# POWER.net
KiCad netlist of a schematic drawn in Altium Designer
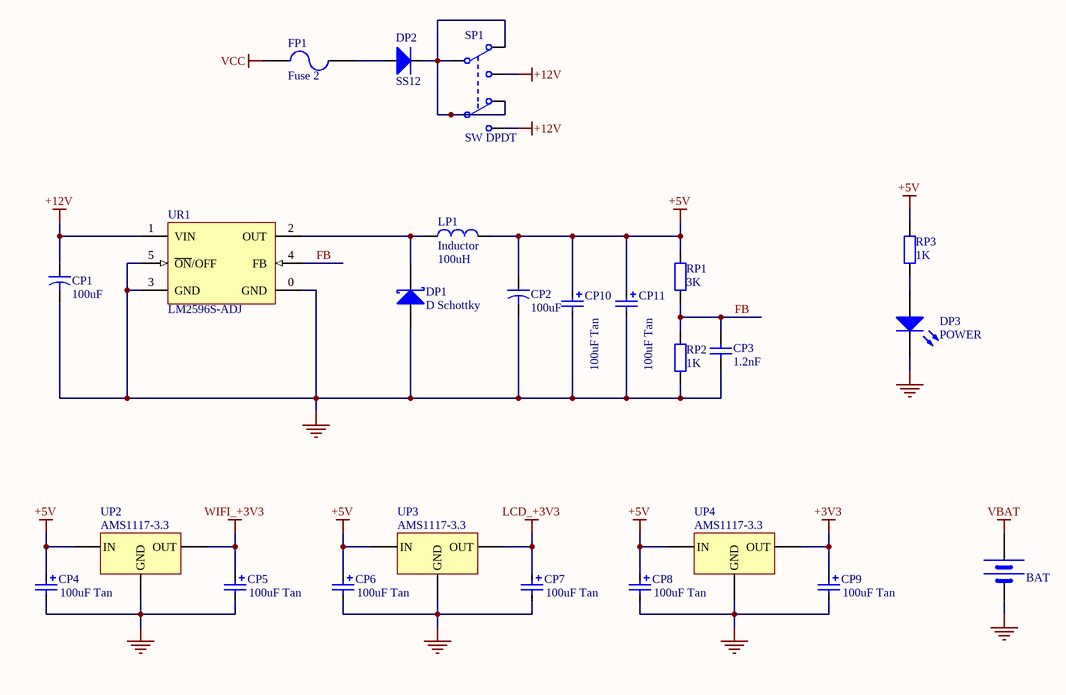
[diagram p0: POWER.SchDoc]

(export (version "E")
  (design (tool "Eeschema 10.0.6"))
  (components
    (comp (ref "BAT") (value "BATT") (footprint "BATM") (libsource (lib "Peace的集成库") (part "BAT")))
    (comp (ref "CP1")
      (value "100uF")
      (footprint "SMD-EC-F10")
      (description "Capacitor")
      (fields (field (name "Comment") "Cap3") (field (name "PUBLISHER") "Altium Limited"))
      (libsource (lib "Peace的集成库") (part "Cap3"))
    )
    (comp (ref "CP2")
      (value "100uF")
      (footprint "SMD-EC-F10")
      (description "Capacitor")
      (fields (field (name "Comment") "Cap3") (field (name "PUBLISHER") "Altium Limited"))
      (libsource (lib "Peace的集成库") (part "Cap3"))
    )
    (comp (ref "CP3")
      (value "1.2nF")
      (footprint "CAPC1608N")
      (description "Capacitor")
      (fields (field (name "Comment") "Cap1") (field (name "PUBLISHER") "Altium Limited"))
      (libsource (lib "Peace的集成库") (part "Cap1"))
    )
    (comp (ref "CP4")
      (value "100uF Tan")
      (footprint "CAP_TAN_B_3518")
      (description "Capacitor")
      (fields (field (name "Comment") "Cap_Tan"))
      (libsource (lib "Peace的集成库") (part "Cap_Tan"))
    )
    (comp (ref "CP5")
      (value "100uF Tan")
      (footprint "CAP_TAN_B_3518")
      (description "Capacitor")
      (fields (field (name "Comment") "Cap_Tan"))
      (libsource (lib "Peace的集成库") (part "Cap_Tan"))
    )
    (comp (ref "CP6")
      (value "100uF Tan")
      (footprint "CAP_TAN_B_3518")
      (description "Capacitor")
      (fields (field (name "Comment") "Cap_Tan"))
      (libsource (lib "Peace的集成库") (part "Cap_Tan"))
    )
    (comp (ref "CP7")
      (value "100uF Tan")
      (footprint "CAP_TAN_B_3518")
      (description "Capacitor")
      (fields (field (name "Comment") "Cap_Tan"))
      (libsource (lib "Peace的集成库") (part "Cap_Tan"))
    )
    (comp (ref "CP8")
      (value "100uF Tan")
      (footprint "CAP_TAN_B_3518")
      (description "Capacitor")
      (fields (field (name "Comment") "Cap_Tan"))
      (libsource (lib "Peace的集成库") (part "Cap_Tan"))
    )
    (comp (ref "CP9")
      (value "100uF Tan")
      (footprint "CAP_TAN_B_3518")
      (description "Capacitor")
      (fields (field (name "Comment") "Cap_Tan"))
      (libsource (lib "Peace的集成库") (part "Cap_Tan"))
    )
    (comp (ref "CP10")
      (value "100uF Tan")
      (footprint "CAP_TAN_B_3518")
      (description "Capacitor")
      (fields (field (name "Comment") "Cap_Tan"))
      (libsource (lib "Peace的集成库") (part "Cap_Tan"))
    )
    (comp (ref "CP11")
      (value "100uF Tan")
      (footprint "CAP_TAN_B_3518")
      (description "Capacitor")
      (fields (field (name "Comment") "Cap_Tan"))
      (libsource (lib "Peace的集成库") (part "Cap_Tan"))
    )
    (comp (ref "DP1")
      (value "D Schottky")
      (footprint "DO-214AC")
      (description "Schottky Diode")
      (fields (field (name "PUBLISHER") "Altium Limited"))
      (libsource (lib "Peace的集成库") (part "D Schottky"))
    )
    (comp (ref "DP2")
      (value "Diode")
      (footprint "DO-214AC")
      (fields (field (name "SMA") "SS12"))
      (libsource (lib "Peace的集成库") (part "Diode"))
    )
    (comp (ref "DP3")
      (value "POWER")
      (footprint "CD2012-0805")
      (description "Typical RED, GREEN, YELLOW, AMBER GaAs LED")
      (fields (field (name "PUBLISHER") "Altium Limited"))
      (libsource (lib "Peace的集成库") (part "LED2"))
    )
    (comp (ref "FP1")
      (value "Fuse 2")
      (footprint "1812")
      (description "Fuse")
      (fields (field (name "PUBLISHER") "Altium Limited"))
      (libsource (lib "Peace的集成库") (part "Fuse 2"))
    )
    (comp (ref "LP1")
      (value "Inductor")
      (footprint "贴片680u")
      (fields (field (name "ALTIUM_VALUE") "100uH") (field (name "PUBLISHER") "Altium Limited"))
      (libsource (lib "Peace的集成库") (part "Inductor"))
    )
    (comp (ref "RP1")
      (value "3K")
      (footprint "RESC1608N")
      (description "Resistor")
      (fields (field (name "Comment") "Res1") (field (name "PUBLISHER") "Altium Limited"))
      (libsource (lib "") (part "Res1_1"))
    )
    (comp (ref "RP2")
      (value "1K")
      (footprint "RESC1608N")
      (description "Resistor")
      (fields (field (name "Comment") "Res1") (field (name "PUBLISHER") "Altium Limited"))
      (libsource (lib "Peace的集成库") (part "Res1"))
    )
    (comp (ref "RP3")
      (value "1K")
      (footprint "RESC1608N")
      (description "Resistor")
      (fields (field (name "Comment") "Res1") (field (name "PUBLISHER") "Altium Limited"))
      (libsource (lib "Peace的集成库") (part "Res1"))
    )
    (comp (ref "SP1")
      (value "SW DPDT")
      (footprint "DPDT-6 x 2.0")
      (description "Switch")
      (fields (field (name "PUBLISHER") "Altium Limited"))
      (libsource (lib "Peace的集成库") (part "SW DPDT"))
    )
    (comp (ref "UP2")
      (value "AMS1117-3.3")
      (footprint "SOT-223_N")
      (libsource (lib "Peace的集成库") (part "AMS1117-3.3"))
    )
    (comp (ref "UP3")
      (value "AMS1117-3.3")
      (footprint "SOT-223_N")
      (libsource (lib "Peace的集成库") (part "AMS1117-3.3"))
    )
    (comp (ref "UP4")
      (value "AMS1117-3.3")
      (footprint "SOT-223_N")
      (libsource (lib "Peace的集成库") (part "AMS1117-3.3"))
    )
    (comp (ref "UR1")
      (value "LM2596S-ADJ")
      (footprint "TO-263")
      (description "SIMPLE SWITCHER 1A Step-Down Voltage Regulator")
      (fields
        (field (name "PARTNUMBER") "LM2575T-ADJ")
        (field (name "MANUFACTURER") "National Semiconductor")
        (field (name "PUBLISHER") "Altium Limited")
      )
      (libsource (lib "Peace的集成库") (part "LM2575T-ADJ"))
    )
  )
  (nets
    (net (code "1") (name "+3V3") (class "Default")
      (node (ref "CP9") (pin "1") (pinfunction "1_1") (pintype "passive"))
      (node (ref "UP4") (pin "2") (pinfunction "OUT_2") (pintype "passive"))
    )
    (net (code "2") (name "+5V") (class "Default")
      (node (ref "CP10") (pin "1") (pinfunction "1_1") (pintype "passive"))
      (node (ref "CP11") (pin "1") (pinfunction "1_1") (pintype "passive"))
      (node (ref "CP2") (pin "1") (pinfunction "1_1") (pintype "passive"))
      (node (ref "CP4") (pin "1") (pinfunction "1_1") (pintype "passive"))
      (node (ref "CP6") (pin "1") (pinfunction "1_1") (pintype "passive"))
      (node (ref "CP8") (pin "1") (pinfunction "1_1") (pintype "passive"))
      (node (ref "LP1") (pin "2") (pinfunction "2_2") (pintype "passive"))
      (node (ref "RP1") (pin "2") (pinfunction "2_2") (pintype "passive"))
      (node (ref "RP3") (pin "1") (pinfunction "1_1") (pintype "passive"))
      (node (ref "UP2") (pin "3") (pinfunction "IN_3") (pintype "passive"))
      (node (ref "UP3") (pin "3") (pinfunction "IN_3") (pintype "passive"))
      (node (ref "UP4") (pin "3") (pinfunction "IN_3") (pintype "passive"))
    )
    (net (code "3") (name "+12V") (class "Default")
      (node (ref "CP1") (pin "1") (pinfunction "1_1") (pintype "passive"))
      (node (ref "SP1") (pin "1") (pinfunction "1_1") (pintype "passive"))
      (node (ref "SP1") (pin "6") (pinfunction "6_6") (pintype "passive"))
      (node (ref "UR1") (pin "1") (pinfunction "VIN_1") (pintype "power_in"))
    )
    (net (code "4") (name "/FB") (class "Default")
      (node (ref "CP3") (pin "2") (pinfunction "2_2") (pintype "passive"))
      (node (ref "RP1") (pin "1") (pinfunction "1_1") (pintype "passive"))
      (node (ref "RP2") (pin "1") (pinfunction "1_1") (pintype "passive"))
      (node (ref "UR1") (pin "4") (pinfunction "FB_4") (pintype "input"))
    )
    (net (code "5") (name "GND") (class "Default")
      (node (ref "BAT") (pin "2") (pinfunction "GND_2") (pintype "passive"))
      (node (ref "CP1") (pin "2") (pinfunction "2_2") (pintype "passive"))
      (node (ref "CP10") (pin "2") (pinfunction "2_2") (pintype "passive"))
      (node (ref "CP11") (pin "2") (pinfunction "2_2") (pintype "passive"))
      (node (ref "CP2") (pin "2") (pinfunction "2_2") (pintype "passive"))
      (node (ref "CP3") (pin "1") (pinfunction "1_1") (pintype "passive"))
      (node (ref "CP4") (pin "2") (pinfunction "2_2") (pintype "passive"))
      (node (ref "CP5") (pin "2") (pinfunction "2_2") (pintype "passive"))
      (node (ref "CP6") (pin "2") (pinfunction "2_2") (pintype "passive"))
      (node (ref "CP7") (pin "2") (pinfunction "2_2") (pintype "passive"))
      (node (ref "CP8") (pin "2") (pinfunction "2_2") (pintype "passive"))
      (node (ref "CP9") (pin "2") (pinfunction "2_2") (pintype "passive"))
      (node (ref "DP1") (pin "1") (pinfunction "A_1") (pintype "passive"))
      (node (ref "DP3") (pin "2") (pinfunction "K_2") (pintype "passive"))
      (node (ref "RP2") (pin "2") (pinfunction "2_2") (pintype "passive"))
      (node (ref "UP2") (pin "1") (pinfunction "GND_1") (pintype "passive"))
      (node (ref "UP3") (pin "1") (pinfunction "GND_1") (pintype "passive"))
      (node (ref "UP4") (pin "1") (pinfunction "GND_1") (pintype "passive"))
      (node (ref "UR1") (pin "0") (pinfunction "GND_0") (pintype "power_in"))
      (node (ref "UR1") (pin "3") (pinfunction "GND_3") (pintype "power_in"))
      (node (ref "UR1") (pin "5") (pinfunction "~{ON}/OFF_5") (pintype "input"))
    )
    (net (code "6") (name "LCD_+3V3") (class "Default")
      (node (ref "CP7") (pin "1") (pinfunction "1_1") (pintype "passive"))
      (node (ref "UP3") (pin "2") (pinfunction "OUT_2") (pintype "passive"))
    )
    (net (code "7") (name "Net-(DP1-K)") (class "Default")
      (node (ref "DP1") (pin "2") (pinfunction "K_2") (pintype "passive"))
      (node (ref "LP1") (pin "1") (pinfunction "1_1") (pintype "passive"))
      (node (ref "UR1") (pin "2") (pinfunction "OUT_2") (pintype "power_in"))
    )
    (net (code "8") (name "Net-(DP2-A)") (class "Default")
      (node (ref "DP2") (pin "1") (pinfunction "A_1") (pintype "passive"))
      (node (ref "FP1") (pin "2") (pinfunction "2_2") (pintype "passive"))
    )
    (net (code "9") (name "Net-(DP2-K)") (class "Default")
      (node (ref "DP2") (pin "2") (pinfunction "K_2") (pintype "passive"))
      (node (ref "SP1") (pin "2") (pinfunction "2_2") (pintype "passive"))
      (node (ref "SP1") (pin "3") (pinfunction "3_3") (pintype "passive"))
      (node (ref "SP1") (pin "4") (pinfunction "4_4") (pintype "passive"))
      (node (ref "SP1") (pin "5") (pinfunction "5_5") (pintype "passive"))
    )
    (net (code "10") (name "Net-(DP3-A)") (class "Default")
      (node (ref "DP3") (pin "1") (pinfunction "A_1") (pintype "passive"))
      (node (ref "RP3") (pin "2") (pinfunction "2_2") (pintype "passive"))
    )
    (net (code "11") (name "VBAT") (class "Default")
      (node (ref "BAT") (pin "1") (pinfunction "VCC_1") (pintype "passive"))
    )
    (net (code "12") (name "VCC") (class "Default")
      (node (ref "FP1") (pin "1") (pinfunction "1_1") (pintype "passive"))
    )
    (net (code "13") (name "WIFI_+3V3") (class "Default")
      (node (ref "CP5") (pin "1") (pinfunction "1_1") (pintype "passive"))
      (node (ref "UP2") (pin "2") (pinfunction "OUT_2") (pintype "passive"))
    )
  )
)
